# dc_aux.net
KiCad netlist of a schematic drawn in Altium Designer
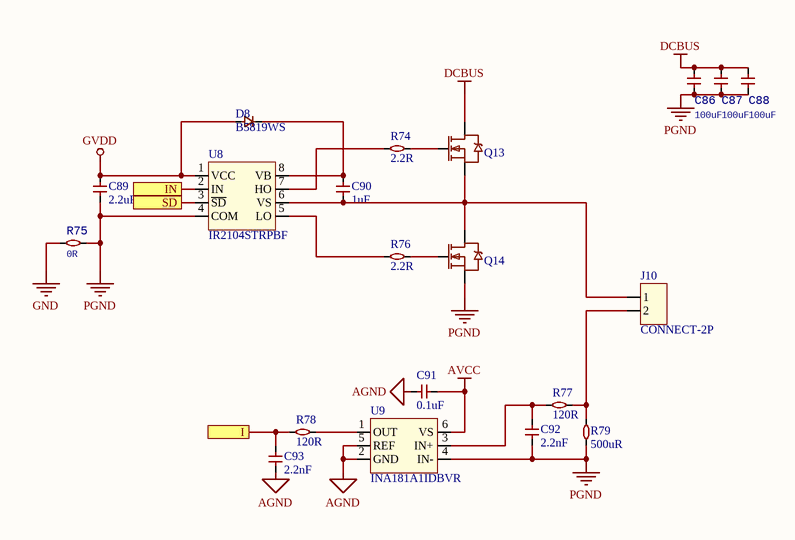
[diagram p0: dc_aux.SchDoc]

(export (version "E")
  (design (tool "Eeschema 10.0.6"))
  (components
    (comp (ref "C86")
      (value "100uF")
      (footprint "C1206")
      (description "贴片电容")
      (fields
        (field (name "MANUFACTURER") "SAMSUNG(三星)")
        (field (name "MANUFACTURER PART") "CL05A105KP5NNND")
      )
      (libsource (lib "schLibrary") (part "CAP"))
    )
    (comp (ref "C87")
      (value "100uF")
      (footprint "C1206")
      (description "贴片电容")
      (fields
        (field (name "MANUFACTURER") "SAMSUNG(三星)")
        (field (name "MANUFACTURER PART") "CL05A105KP5NNND")
      )
      (libsource (lib "schLibrary") (part "CAP"))
    )
    (comp (ref "C88")
      (value "100uF")
      (footprint "C1206")
      (description "贴片电容")
      (fields
        (field (name "MANUFACTURER") "SAMSUNG(三星)")
        (field (name "MANUFACTURER PART") "CL05A105KP5NNND")
      )
      (libsource (lib "schLibrary") (part "CAP"))
    )
    (comp (ref "C89")
      (value "2.2uF")
      (footprint "C0402")
      (description "贴片电容")
      (fields
        (field (name "MANUFACTURER") "SAMSUNG(三星)")
        (field (name "MANUFACTURER PART") "CL05A105KP5NNND")
      )
      (libsource (lib "schLibrary") (part "CAP"))
    )
    (comp (ref "C90")
      (value "1uF")
      (footprint "C0402")
      (description "贴片电容")
      (fields
        (field (name "MANUFACTURER") "SAMSUNG(三星)")
        (field (name "MANUFACTURER PART") "CL05A105KP5NNND")
      )
      (libsource (lib "schLibrary") (part "CAP"))
    )
    (comp (ref "C91")
      (value "0.1uF")
      (footprint "C0402")
      (description "贴片电容")
      (fields
        (field (name "MANUFACTURER") "SAMSUNG(三星)")
        (field (name "MANUFACTURER PART") "CL05A105KP5NNND")
      )
      (libsource (lib "schLibrary") (part "CAP"))
    )
    (comp (ref "C92")
      (value "2.2nF")
      (footprint "C0402")
      (description "贴片电容")
      (fields
        (field (name "MANUFACTURER") "SAMSUNG(三星)")
        (field (name "MANUFACTURER PART") "CL05A105KP5NNND")
      )
      (libsource (lib "schLibrary") (part "CAP"))
    )
    (comp (ref "C93")
      (value "2.2nF")
      (footprint "C0402")
      (description "贴片电容")
      (fields
        (field (name "MANUFACTURER") "SAMSUNG(三星)")
        (field (name "MANUFACTURER PART") "CL05A105KP5NNND")
      )
      (libsource (lib "schLibrary") (part "CAP"))
    )
    (comp (ref "D8")
      (value "B5819WS")
      (footprint "SOD-323")
      (description "通用二极管")
      (fields
        (field (name "MANUFACTURER") "SAMSUNG(三星)")
        (field (name "MANUFACTURER PART") "CL05A105KP5NNND")
      )
      (libsource (lib "schLibrary") (part "DIO"))
    )
    (comp (ref "J10")
      (value "CONNECT-2P")
      (footprint "CONNECT-2P")
      (description "连接器")
      (libsource (lib "schLibrary") (part "CONNECT-2P"))
    )
    (comp (ref "Q13")
      (value "AP68N06G")
      (footprint "SOT-23-3")
      (description "N沟道功率mos管")
      (fields (field (name "MANUFACTURER") "BORN(伯恩半导体)") (field (name "MANUFACTURER PART") "AO3401A"))
      (libsource (lib "schLibrary") (part "NMOS"))
    )
    (comp (ref "Q14")
      (value "AP68N06G")
      (footprint "SOT-23-3")
      (description "N沟道功率mos管")
      (fields (field (name "MANUFACTURER") "BORN(伯恩半导体)") (field (name "MANUFACTURER PART") "AO3401A"))
      (libsource (lib "schLibrary") (part "NMOS"))
    )
    (comp (ref "R74")
      (value "2.2R")
      (footprint "R0402")
      (description "贴片电阻0603")
      (fields
        (field (name "MANUFACTURER") "UNI-ROYAL(厚声)")
        (field (name "MANUFACTURER PART") "0402WGF1001TCE")
      )
      (libsource (lib "schLibrary") (part "RES"))
    )
    (comp (ref "R75")
      (value "0R")
      (footprint "R0402")
      (description "贴片电阻")
      (fields
        (field (name "MANUFACTURER") "UNI-ROYAL(厚声)")
        (field (name "MANUFACTURER PART") "0402WGF1001TCE")
      )
      (libsource (lib "schLibrary") (part "RES"))
    )
    (comp (ref "R76")
      (value "2.2R")
      (footprint "R0402")
      (description "贴片电阻0603")
      (fields
        (field (name "MANUFACTURER") "UNI-ROYAL(厚声)")
        (field (name "MANUFACTURER PART") "0402WGF1001TCE")
      )
      (libsource (lib "schLibrary") (part "RES"))
    )
    (comp (ref "R77")
      (value "120R")
      (footprint "R0402")
      (description "贴片电阻0603")
      (fields
        (field (name "MANUFACTURER") "UNI-ROYAL(厚声)")
        (field (name "MANUFACTURER PART") "0402WGF1001TCE")
      )
      (libsource (lib "schLibrary") (part "RES"))
    )
    (comp (ref "R78")
      (value "120R")
      (footprint "R0402")
      (description "贴片电阻")
      (fields
        (field (name "MANUFACTURER") "UNI-ROYAL(厚声)")
        (field (name "MANUFACTURER PART") "0402WGF1001TCE")
      )
      (libsource (lib "schLibrary") (part "RES"))
    )
    (comp (ref "R79")
      (value "500uR")
      (footprint "R2512")
      (description "贴片电阻\r\n2512")
      (fields
        (field (name "MANUFACTURER") "UNI-ROYAL(厚声)")
        (field (name "MANUFACTURER PART") "0402WGF1001TCE")
      )
      (libsource (lib "schLibrary") (part "RES"))
    )
    (comp (ref "U8")
      (value "IR2104STRPBF")
      (footprint "SOIC-8")
      (description "栅极驱动IC\r\nInfineon\r\nSOP-8")
      (libsource (lib "schLibrary") (part "IR2104STRPBF"))
    )
    (comp (ref "U9")
      (value "INA181A1IDBVR")
      (footprint "SOT-23-6")
      (description "电流感应放大器\r\nTI(德州仪器)")
      (libsource (lib "schLibrary") (part "INA181Ax"))
    )
  )
  (nets
    (net (code "1") (name "/I") (class "Default")
      (node (ref "C93") (pin "2") (pinfunction "2_2") (pintype "passive"))
      (node (ref "R78") (pin "1") (pinfunction "1_1") (pintype "passive"))
    )
    (net (code "2") (name "/IN") (class "Default")
      (node (ref "U8") (pin "2") (pinfunction "IN_2") (pintype "passive"))
    )
    (net (code "3") (name "/SD") (class "Default")
      (node (ref "U8") (pin "3") (pinfunction "~{SD}_3") (pintype "passive"))
    )
    (net (code "4") (name "AGND") (class "Default")
      (node (ref "C91") (pin "1") (pinfunction "1_1") (pintype "passive"))
      (node (ref "C93") (pin "1") (pinfunction "1_1") (pintype "passive"))
      (node (ref "U9") (pin "2") (pinfunction "GND_2") (pintype "passive"))
      (node (ref "U9") (pin "5") (pinfunction "REF_5") (pintype "passive"))
    )
    (net (code "5") (name "AVCC") (class "Default")
      (node (ref "C91") (pin "2") (pinfunction "2_2") (pintype "passive"))
      (node (ref "U9") (pin "6") (pinfunction "VS_6") (pintype "passive"))
    )
    (net (code "6") (name "DCBUS") (class "Default")
      (node (ref "C86") (pin "1") (pinfunction "1_1") (pintype "passive"))
      (node (ref "C87") (pin "1") (pinfunction "1_1") (pintype "passive"))
      (node (ref "C88") (pin "1") (pinfunction "1_1") (pintype "passive"))
      (node (ref "Q13") (pin "3") (pinfunction "D_3") (pintype "passive"))
    )
    (net (code "7") (name "GND") (class "Default")
      (node (ref "R75") (pin "1") (pinfunction "1_1") (pintype "passive"))
    )
    (net (code "8") (name "GVDD") (class "Default")
      (node (ref "C89") (pin "1") (pinfunction "1_1") (pintype "passive"))
      (node (ref "D8") (pin "2") (pinfunction "2_2") (pintype "passive"))
      (node (ref "U8") (pin "1") (pinfunction "VCC_1") (pintype "passive"))
    )
    (net (code "9") (name "Net-(J10-Pad2)") (class "Default")
      (node (ref "J10") (pin "2") (pinfunction "2_2") (pintype "passive"))
      (node (ref "R77") (pin "2") (pinfunction "2_2") (pintype "passive"))
      (node (ref "R79") (pin "1") (pinfunction "1_1") (pintype "passive"))
    )
    (net (code "10") (name "Net-(Q13-G)") (class "Default")
      (node (ref "Q13") (pin "1") (pinfunction "G_1") (pintype "passive"))
      (node (ref "R74") (pin "2") (pinfunction "2_2") (pintype "passive"))
    )
    (net (code "11") (name "Net-(Q13-S)") (class "Default")
      (node (ref "C90") (pin "2") (pinfunction "2_2") (pintype "passive"))
      (node (ref "J10") (pin "1") (pinfunction "1_1") (pintype "passive"))
      (node (ref "Q13") (pin "2") (pinfunction "S_2") (pintype "passive"))
      (node (ref "Q14") (pin "3") (pinfunction "D_3") (pintype "passive"))
      (node (ref "U8") (pin "6") (pinfunction "VS_6") (pintype "passive"))
    )
    (net (code "12") (name "Net-(Q14-G)") (class "Default")
      (node (ref "Q14") (pin "1") (pinfunction "G_1") (pintype "passive"))
      (node (ref "R76") (pin "2") (pinfunction "2_2") (pintype "passive"))
    )
    (net (code "13") (name "Net-(U8-HO)") (class "Default")
      (node (ref "R74") (pin "1") (pinfunction "1_1") (pintype "passive"))
      (node (ref "U8") (pin "7") (pinfunction "HO_7") (pintype "passive"))
    )
    (net (code "14") (name "Net-(U8-LO)") (class "Default")
      (node (ref "R76") (pin "1") (pinfunction "1_1") (pintype "passive"))
      (node (ref "U8") (pin "5") (pinfunction "LO_5") (pintype "passive"))
    )
    (net (code "15") (name "Net-(U8-VB)") (class "Default")
      (node (ref "C90") (pin "1") (pinfunction "1_1") (pintype "passive"))
      (node (ref "D8") (pin "1") (pinfunction "1_1") (pintype "passive"))
      (node (ref "U8") (pin "8") (pinfunction "VB_8") (pintype "passive"))
    )
    (net (code "16") (name "Net-(U9-IN+)") (class "Default")
      (node (ref "C92") (pin "1") (pinfunction "1_1") (pintype "passive"))
      (node (ref "R77") (pin "1") (pinfunction "1_1") (pintype "passive"))
      (node (ref "U9") (pin "3") (pinfunction "IN+_3") (pintype "passive"))
    )
    (net (code "17") (name "Net-(U9-OUT)") (class "Default")
      (node (ref "R78") (pin "2") (pinfunction "2_2") (pintype "passive"))
      (node (ref "U9") (pin "1") (pinfunction "OUT_1") (pintype "passive"))
    )
    (net (code "18") (name "PGND") (class "Default")
      (node (ref "C86") (pin "2") (pinfunction "2_2") (pintype "passive"))
      (node (ref "C87") (pin "2") (pinfunction "2_2") (pintype "passive"))
      (node (ref "C88") (pin "2") (pinfunction "2_2") (pintype "passive"))
      (node (ref "C89") (pin "2") (pinfunction "2_2") (pintype "passive"))
      (node (ref "C92") (pin "2") (pinfunction "2_2") (pintype "passive"))
      (node (ref "Q14") (pin "2") (pinfunction "S_2") (pintype "passive"))
      (node (ref "R75") (pin "2") (pinfunction "2_2") (pintype "passive"))
      (node (ref "R79") (pin "2") (pinfunction "2_2") (pintype "passive"))
      (node (ref "U8") (pin "4") (pinfunction "COM_4") (pintype "passive"))
      (node (ref "U9") (pin "4") (pinfunction "IN-_4") (pintype "passive"))
    )
  )
)
